# Module_Connector_Female.net
KiCad netlist of a schematic drawn in Altium Designer
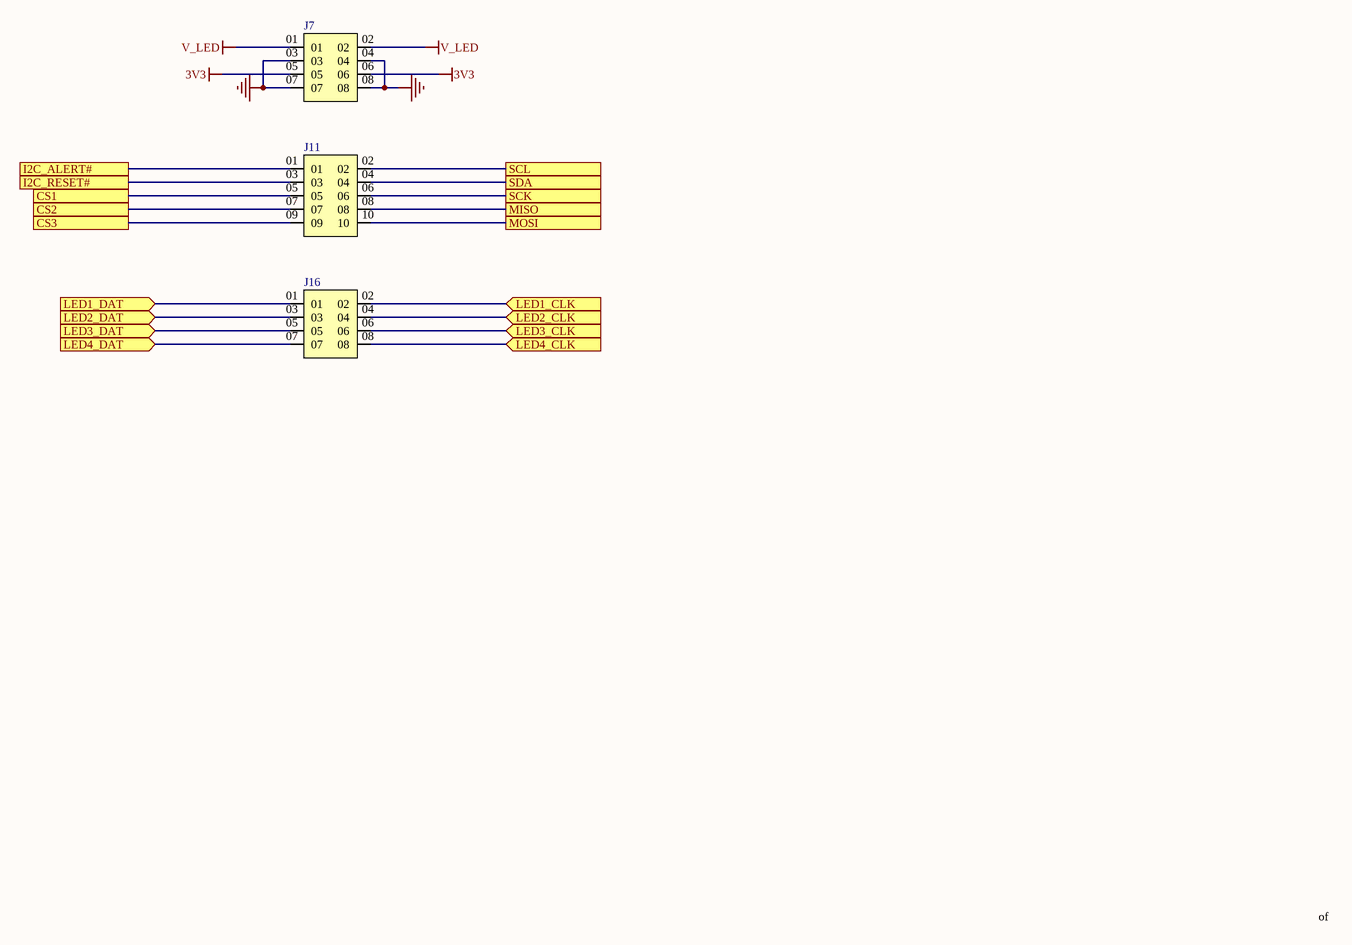
[diagram p0: Module Connector Female.SchDoc]

(export (version "E")
  (design (tool "Eeschema 10.0.6"))
  (components
    (comp (ref "J7")
      (value "Socket 4x2 0.1\" RA")
      (footprint "Socket 4x2 0.1\" RA")
      (libsource (lib "Equus Computer Systems") (part "Header 4x2"))
    )
    (comp (ref "J11")
      (value "Socket 5x2 0.1\" RA")
      (footprint "Socket 5x2 0.1\" RA Through Hole")
      (libsource (lib "Equus Computer Systems") (part "Header 5x2 0.1{dblquote}"))
    )
    (comp (ref "J16")
      (value "Socket 4x2 0.1\" RA")
      (footprint "Socket 4x2 0.1\" RA")
      (libsource (lib "Equus Computer Systems") (part "Header 4x2"))
    )
  )
  (nets
    (net (code "1") (name "/CS1") (class "Default")
      (node (ref "J11") (pin "05") (pinfunction "05_05") (pintype "passive"))
    )
    (net (code "2") (name "/CS2") (class "Default")
      (node (ref "J11") (pin "07") (pinfunction "07_07") (pintype "passive"))
    )
    (net (code "3") (name "/CS3") (class "Default")
      (node (ref "J11") (pin "09") (pinfunction "09_09") (pintype "passive"))
    )
    (net (code "4") (name "/I2C_ALERT#") (class "Default")
      (node (ref "J11") (pin "01") (pinfunction "01_01") (pintype "passive"))
    )
    (net (code "5") (name "/I2C_RESET#") (class "Default")
      (node (ref "J11") (pin "03") (pinfunction "03_03") (pintype "passive"))
    )
    (net (code "6") (name "/LED1_CLK") (class "Default")
      (node (ref "J16") (pin "02") (pinfunction "02_02") (pintype "passive"))
    )
    (net (code "7") (name "/LED1_DAT") (class "Default")
      (node (ref "J16") (pin "01") (pinfunction "01_01") (pintype "passive"))
    )
    (net (code "8") (name "/LED2_CLK") (class "Default")
      (node (ref "J16") (pin "04") (pinfunction "04_04") (pintype "passive"))
    )
    (net (code "9") (name "/LED2_DAT") (class "Default")
      (node (ref "J16") (pin "03") (pinfunction "03_03") (pintype "passive"))
    )
    (net (code "10") (name "/LED3_CLK") (class "Default")
      (node (ref "J16") (pin "06") (pinfunction "06_06") (pintype "passive"))
    )
    (net (code "11") (name "/LED3_DAT") (class "Default")
      (node (ref "J16") (pin "05") (pinfunction "05_05") (pintype "passive"))
    )
    (net (code "12") (name "/LED4_CLK") (class "Default")
      (node (ref "J16") (pin "08") (pinfunction "08_08") (pintype "passive"))
    )
    (net (code "13") (name "/LED4_DAT") (class "Default")
      (node (ref "J16") (pin "07") (pinfunction "07_07") (pintype "passive"))
    )
    (net (code "14") (name "/MISO") (class "Default")
      (node (ref "J11") (pin "08") (pinfunction "08_08") (pintype "passive"))
    )
    (net (code "15") (name "/MOSI") (class "Default")
      (node (ref "J11") (pin "10") (pinfunction "10_10") (pintype "passive"))
    )
    (net (code "16") (name "/SCK") (class "Default")
      (node (ref "J11") (pin "06") (pinfunction "06_06") (pintype "passive"))
    )
    (net (code "17") (name "/SCL") (class "Default")
      (node (ref "J11") (pin "02") (pinfunction "02_02") (pintype "passive"))
    )
    (net (code "18") (name "/SDA") (class "Default")
      (node (ref "J11") (pin "04") (pinfunction "04_04") (pintype "passive"))
    )
    (net (code "19") (name "3V3") (class "Default")
      (node (ref "J7") (pin "05") (pinfunction "05_05") (pintype "passive"))
      (node (ref "J7") (pin "06") (pinfunction "06_06") (pintype "passive"))
    )
    (net (code "20") (name "GND") (class "Default")
      (node (ref "J7") (pin "03") (pinfunction "03_03") (pintype "passive"))
      (node (ref "J7") (pin "04") (pinfunction "04_04") (pintype "passive"))
      (node (ref "J7") (pin "07") (pinfunction "07_07") (pintype "passive"))
      (node (ref "J7") (pin "08") (pinfunction "08_08") (pintype "passive"))
    )
    (net (code "21") (name "V_LED") (class "Default")
      (node (ref "J7") (pin "01") (pinfunction "01_01") (pintype "passive"))
      (node (ref "J7") (pin "02") (pinfunction "02_02") (pintype "passive"))
    )
  )
)
